# WeMos-meteo_v1_1.net
KiCad netlist of a schematic drawn in EAGLE
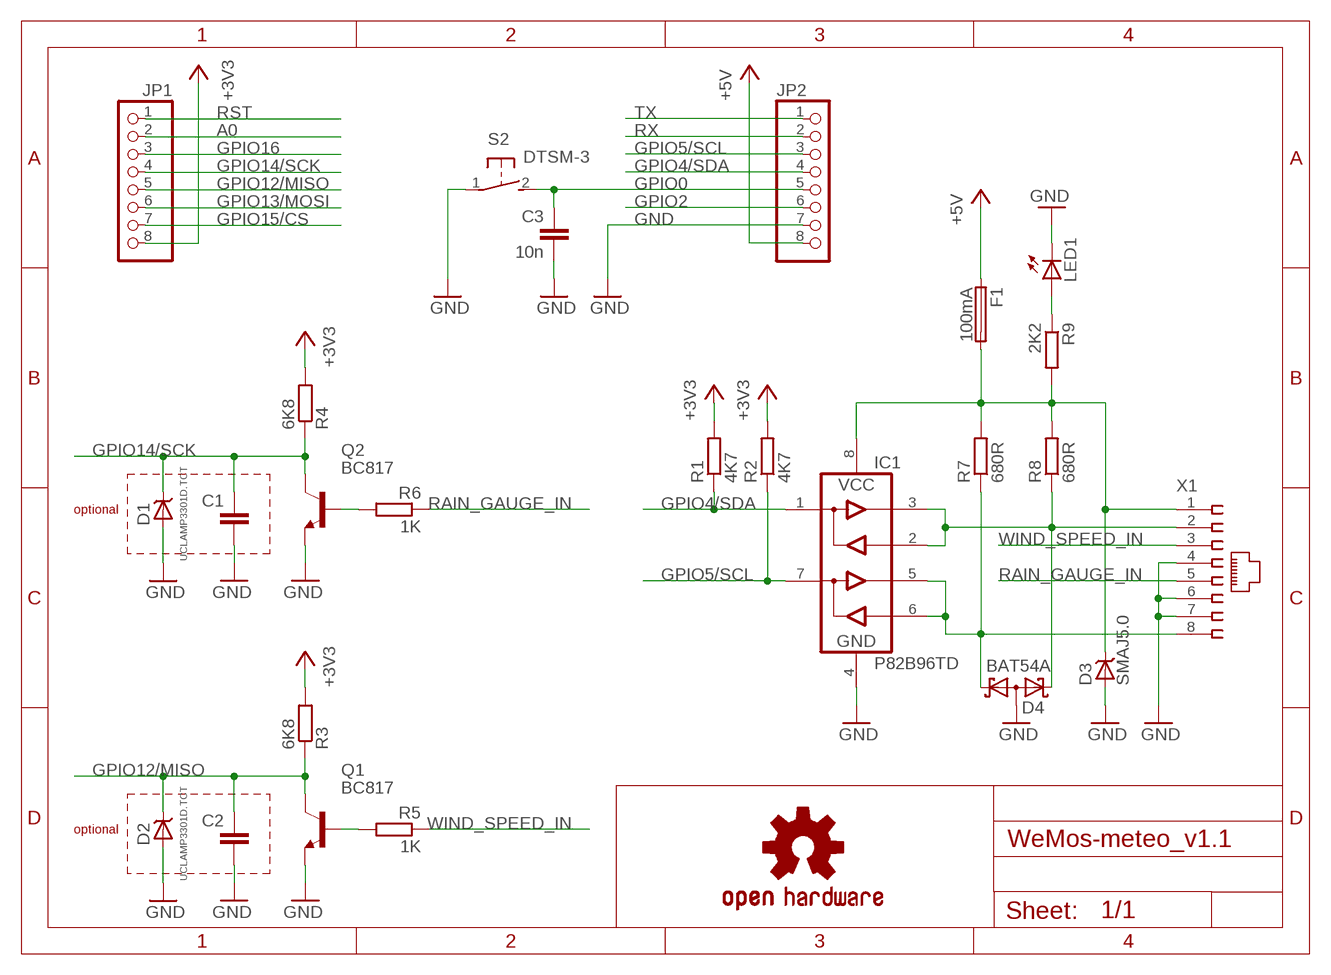
[diagram p0: schematic, sheet 1]

(export (version "E")
  (design (tool "Eeschema 10.0.6"))
  (components
    (comp (ref "C1")
      (value "C-EUC0805")
      (footprint "eagle-import:C0805")
      (libsource (lib "eagle-import") (part "C-EUC0805"))
    )
    (comp (ref "C2")
      (value "C-EUC0805")
      (footprint "eagle-import:C0805")
      (libsource (lib "eagle-import") (part "C-EUC0805"))
    )
    (comp (ref "C3")
      (value "10n")
      (footprint "eagle-import:C0805")
      (libsource (lib "eagle-import") (part "C-EUC0805"))
    )
    (comp (ref "D1")
      (value "UCLAMP3301D.TCT")
      (footprint "eagle-import:SOD323")
      (libsource (lib "eagle-import") (part "UCLAMP3301?.TCTD"))
    )
    (comp (ref "D2")
      (value "UCLAMP3301D.TCT")
      (footprint "eagle-import:SOD323")
      (libsource (lib "eagle-import") (part "UCLAMP3301?.TCTD"))
    )
    (comp (ref "D3")
      (value "SMAJ5.0")
      (footprint "eagle-import:DO214AC")
      (libsource (lib "eagle-import") (part "SM?JA5.0"))
    )
    (comp (ref "D4")
      (value "BAT54A")
      (footprint "eagle-import:SOT23")
      (libsource (lib "eagle-import") (part "BAT54A"))
    )
    (comp (ref "F1")
      (value "100mA")
      (footprint "eagle-import:19560")
      (libsource (lib "eagle-import") (part "19560"))
    )
    (comp (ref "IC1")
      (value "P82B96TD")
      (footprint "eagle-import:SO08")
      (libsource (lib "eagle-import") (part "P82B96?TD"))
    )
    (comp (ref "JP1")
      (value "PINHD-1X08_2.54-S")
      (footprint "eagle-import:1X08-S")
      (libsource (lib "eagle-import") (part "PINHD-1X08_2.54-S"))
    )
    (comp (ref "JP2")
      (value "PINHD-1X08_2.54-S")
      (footprint "eagle-import:1X08-S")
      (libsource (lib "eagle-import") (part "PINHD-1X08_2.54-S"))
    )
    (comp (ref "LED1")
      (value "LED0805")
      (footprint "eagle-import:LED0805")
      (libsource (lib "eagle-import") (part "LED0805"))
    )
    (comp (ref "LOGO1")
      (value "OSHW-LOGOMINI")
      (footprint "eagle-import:OSHW-LOGO-MINI")
      (libsource (lib "eagle-import") (part "OSHW-LOGOMINI"))
    )
    (comp (ref "Q1")
      (value "BC817")
      (footprint "eagle-import:SOT23-BEC")
      (libsource (lib "eagle-import") (part "BC817SMD-40"))
    )
    (comp (ref "Q2")
      (value "BC817")
      (footprint "eagle-import:SOT23-BEC")
      (libsource (lib "eagle-import") (part "BC817SMD-40"))
    )
    (comp (ref "R1")
      (value "4K7")
      (footprint "eagle-import:R0805")
      (libsource (lib "eagle-import") (part "R-EU_R0805"))
    )
    (comp (ref "R2")
      (value "4K7")
      (footprint "eagle-import:R0805")
      (libsource (lib "eagle-import") (part "R-EU_R0805"))
    )
    (comp (ref "R3")
      (value "6K8")
      (footprint "eagle-import:R0805")
      (libsource (lib "eagle-import") (part "R-EU_R0805"))
    )
    (comp (ref "R4")
      (value "6K8")
      (footprint "eagle-import:R0805")
      (libsource (lib "eagle-import") (part "R-EU_R0805"))
    )
    (comp (ref "R5")
      (value "1K")
      (footprint "eagle-import:R0805")
      (libsource (lib "eagle-import") (part "R-EU_R0805"))
    )
    (comp (ref "R6")
      (value "1K")
      (footprint "eagle-import:R0805")
      (libsource (lib "eagle-import") (part "R-EU_R0805"))
    )
    (comp (ref "R7")
      (value "680R")
      (footprint "eagle-import:R0805")
      (libsource (lib "eagle-import") (part "R-EU_R0805"))
    )
    (comp (ref "R8")
      (value "680R")
      (footprint "eagle-import:R0805")
      (libsource (lib "eagle-import") (part "R-EU_R0805"))
    )
    (comp (ref "R9")
      (value "2K2")
      (footprint "eagle-import:R0805")
      (libsource (lib "eagle-import") (part "R-EU_R0805"))
    )
    (comp (ref "S2")
      (value "DTSM-3")
      (footprint "eagle-import:DTSM-3")
      (libsource (lib "eagle-import") (part "DTSM-3"))
    )
    (comp (ref "X1")
      (value "RJ-45")
      (footprint "eagle-import:95501")
      (libsource (lib "eagle-import") (part "RJ-45"))
    )
  )
  (nets
    (net (code "1") (name "+3V3") (class "Default")
      (node (ref "JP1") (pin "8") (pinfunction "8_8") (pintype "passive"))
      (node (ref "R1") (pin "2") (pinfunction "2_2") (pintype "passive"))
      (node (ref "R2") (pin "2") (pinfunction "2_2") (pintype "passive"))
      (node (ref "R3") (pin "2") (pinfunction "2_2") (pintype "passive"))
      (node (ref "R4") (pin "2") (pinfunction "2_2") (pintype "passive"))
    )
    (net (code "2") (name "+5V") (class "Default")
      (node (ref "F1") (pin "1") (pinfunction "1_1") (pintype "passive"))
      (node (ref "JP2") (pin "8") (pinfunction "8_8") (pintype "passive"))
    )
    (net (code "3") (name "/A0") (class "Default")
      (node (ref "JP1") (pin "2") (pinfunction "2_2") (pintype "passive"))
    )
    (net (code "4") (name "/GPIO0") (class "Default")
      (node (ref "C3") (pin "1") (pinfunction "1_1") (pintype "passive"))
      (node (ref "JP2") (pin "5") (pinfunction "5_5") (pintype "passive"))
      (node (ref "S2") (pin "2") (pinfunction "2_2") (pintype "passive"))
    )
    (net (code "5") (name "/GPIO2") (class "Default")
      (node (ref "JP2") (pin "6") (pinfunction "6_6") (pintype "passive"))
    )
    (net (code "6") (name "/GPIO4{slash}SDA") (class "Default")
      (node (ref "IC1") (pin "1") (pinfunction "SX_1") (pintype "input"))
      (node (ref "JP2") (pin "4") (pinfunction "4_4") (pintype "passive"))
      (node (ref "R1") (pin "1") (pinfunction "1_1") (pintype "passive"))
    )
    (net (code "7") (name "/GPIO5{slash}SCL") (class "Default")
      (node (ref "IC1") (pin "7") (pinfunction "SY_7") (pintype "input"))
      (node (ref "JP2") (pin "3") (pinfunction "3_3") (pintype "passive"))
      (node (ref "R2") (pin "1") (pinfunction "1_1") (pintype "passive"))
    )
    (net (code "8") (name "/GPIO12{slash}MISO") (class "Default")
      (node (ref "C2") (pin "1") (pinfunction "1_1") (pintype "passive"))
      (node (ref "D2") (pin "C") (pinfunction "C_C") (pintype "passive"))
      (node (ref "JP1") (pin "5") (pinfunction "5_5") (pintype "passive"))
      (node (ref "Q1") (pin "C") (pinfunction "C_C") (pintype "passive"))
      (node (ref "R3") (pin "1") (pinfunction "1_1") (pintype "passive"))
    )
    (net (code "9") (name "/GPIO13{slash}MOSI") (class "Default")
      (node (ref "JP1") (pin "6") (pinfunction "6_6") (pintype "passive"))
    )
    (net (code "10") (name "/GPIO14{slash}SCK") (class "Default")
      (node (ref "C1") (pin "1") (pinfunction "1_1") (pintype "passive"))
      (node (ref "D1") (pin "C") (pinfunction "C_C") (pintype "passive"))
      (node (ref "JP1") (pin "4") (pinfunction "4_4") (pintype "passive"))
      (node (ref "Q2") (pin "C") (pinfunction "C_C") (pintype "passive"))
      (node (ref "R4") (pin "1") (pinfunction "1_1") (pintype "passive"))
    )
    (net (code "11") (name "/GPIO15{slash}CS") (class "Default")
      (node (ref "JP1") (pin "7") (pinfunction "7_7") (pintype "passive"))
    )
    (net (code "12") (name "/GPIO16") (class "Default")
      (node (ref "JP1") (pin "3") (pinfunction "3_3") (pintype "passive"))
    )
    (net (code "13") (name "/RAIN_GAUGE_IN") (class "Default")
      (node (ref "R6") (pin "1") (pinfunction "1_1") (pintype "passive"))
      (node (ref "X1") (pin "5") (pinfunction "5_5") (pintype "passive"))
    )
    (net (code "14") (name "/RST") (class "Default")
      (node (ref "JP1") (pin "1") (pinfunction "1_1") (pintype "passive"))
    )
    (net (code "15") (name "/RX") (class "Default")
      (node (ref "JP2") (pin "2") (pinfunction "2_2") (pintype "passive"))
    )
    (net (code "16") (name "/TX") (class "Default")
      (node (ref "JP2") (pin "1") (pinfunction "1_1") (pintype "passive"))
    )
    (net (code "17") (name "/WIND_SPEED_IN") (class "Default")
      (node (ref "R5") (pin "1") (pinfunction "1_1") (pintype "passive"))
      (node (ref "X1") (pin "3") (pinfunction "3_3") (pintype "passive"))
    )
    (net (code "18") (name "GND") (class "Default")
      (node (ref "C1") (pin "2") (pinfunction "2_2") (pintype "passive"))
      (node (ref "C2") (pin "2") (pinfunction "2_2") (pintype "passive"))
      (node (ref "C3") (pin "2") (pinfunction "2_2") (pintype "passive"))
      (node (ref "D1") (pin "A") (pinfunction "A_A") (pintype "passive"))
      (node (ref "D2") (pin "A") (pinfunction "A_A") (pintype "passive"))
      (node (ref "D3") (pin "A") (pinfunction "A_A") (pintype "passive"))
      (node (ref "D4") (pin "3") (pinfunction "AA_3") (pintype "passive"))
      (node (ref "IC1") (pin "4") (pinfunction "GND_4") (pintype "power_in"))
      (node (ref "JP2") (pin "7") (pinfunction "7_7") (pintype "passive"))
      (node (ref "LED1") (pin "C") (pinfunction "C_C") (pintype "passive"))
      (node (ref "Q1") (pin "E") (pinfunction "E_E") (pintype "passive"))
      (node (ref "Q2") (pin "E") (pinfunction "E_E") (pintype "passive"))
      (node (ref "S2") (pin "1") (pinfunction "1_1") (pintype "passive"))
      (node (ref "X1") (pin "4") (pinfunction "4_4") (pintype "passive"))
      (node (ref "X1") (pin "6") (pinfunction "6_6") (pintype "passive"))
      (node (ref "X1") (pin "7") (pinfunction "7_7") (pintype "passive"))
    )
    (net (code "19") (name "Net-(D4-K1)") (class "Default")
      (node (ref "D4") (pin "1") (pinfunction "K1_1") (pintype "passive"))
      (node (ref "IC1") (pin "5") (pinfunction "TY_5") (pintype "open_collector"))
      (node (ref "IC1") (pin "6") (pinfunction "RY_6") (pintype "open_collector"))
      (node (ref "R7") (pin "1") (pinfunction "1_1") (pintype "passive"))
      (node (ref "X1") (pin "8") (pinfunction "8_8") (pintype "passive"))
    )
    (net (code "20") (name "Net-(D4-K2)") (class "Default")
      (node (ref "D4") (pin "2") (pinfunction "K2_2") (pintype "passive"))
      (node (ref "IC1") (pin "2") (pinfunction "RX_2") (pintype "open_collector"))
      (node (ref "IC1") (pin "3") (pinfunction "TX_3") (pintype "open_collector"))
      (node (ref "R8") (pin "1") (pinfunction "1_1") (pintype "passive"))
      (node (ref "X1") (pin "2") (pinfunction "2_2") (pintype "passive"))
    )
    (net (code "21") (name "Net-(IC1-VCC)") (class "Default")
      (node (ref "D3") (pin "C") (pinfunction "C_C") (pintype "passive"))
      (node (ref "F1") (pin "2") (pinfunction "2_2") (pintype "passive"))
      (node (ref "IC1") (pin "8") (pinfunction "VCC_8") (pintype "power_in"))
      (node (ref "R7") (pin "2") (pinfunction "2_2") (pintype "passive"))
      (node (ref "R8") (pin "2") (pinfunction "2_2") (pintype "passive"))
      (node (ref "R9") (pin "2") (pinfunction "2_2") (pintype "passive"))
      (node (ref "X1") (pin "1") (pinfunction "1_1") (pintype "passive"))
    )
    (net (code "22") (name "Net-(LED1-PadA)") (class "Default")
      (node (ref "LED1") (pin "A") (pinfunction "A_A") (pintype "passive"))
      (node (ref "R9") (pin "1") (pinfunction "1_1") (pintype "passive"))
    )
    (net (code "23") (name "Net-(Q1-PadB)") (class "Default")
      (node (ref "Q1") (pin "B") (pinfunction "B_B") (pintype "passive"))
      (node (ref "R5") (pin "2") (pinfunction "2_2") (pintype "passive"))
    )
    (net (code "24") (name "Net-(Q2-PadB)") (class "Default")
      (node (ref "Q2") (pin "B") (pinfunction "B_B") (pintype "passive"))
      (node (ref "R6") (pin "2") (pinfunction "2_2") (pintype "passive"))
    )
  )
)
